# gydrodrive_currentSource.net
KiCad netlist of a schematic drawn in Altium Designer
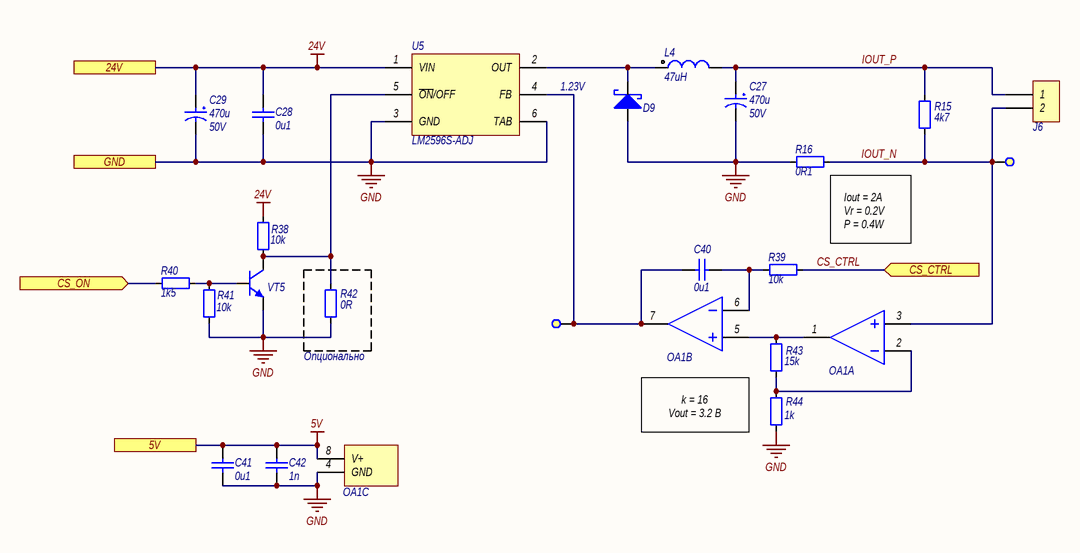
[diagram p0: gydrodrive_currentSource.SchDoc]

(export (version "E")
  (design (tool "Eeschema 10.0.6"))
  (components
    (comp (ref "C27")
      (value "JRB1H471M05001000200000B")
      (footprint "ECAP1020")
      (description "Конденсатор электролитический")
      (fields (field (name "CAPACITANCE") "470u") (field (name "VOLTAGE") "50V"))
      (libsource (lib "StdLib") (part "CAP_POL"))
    )
    (comp (ref "C28")
      (value "CAP_0805")
      (footprint "CAPC2012-0805M")
      (description "Конденсатор керамический, корпус 0805")
      (fields
        (field (name "CAPACITANCE") "0u1")
        (field (name "PART NUMBER") "CAPC_0805")
        (field (name "VOLTAGE") "50V")
      )
      (libsource (lib "StdLib") (part "CAP"))
    )
    (comp (ref "C29")
      (value "JRB1H471M05001000200000B")
      (footprint "ECAP1020")
      (description "Конденсатор электролитический")
      (fields (field (name "CAPACITANCE") "470u") (field (name "VOLTAGE") "50V"))
      (libsource (lib "StdLib") (part "CAP_POL"))
    )
    (comp (ref "C40")
      (value "CAP_0805")
      (footprint "CAPC2012-0805M")
      (description "Конденсатор керамический, корпус 0805")
      (fields
        (field (name "CAPACITANCE") "0u1")
        (field (name "PART NUMBER") "CAPC_0805")
        (field (name "VOLTAGE") "50V")
      )
      (libsource (lib "StdLib") (part "CAP"))
    )
    (comp (ref "C41")
      (value "CAP_0805")
      (footprint "CAPC2012-0805M")
      (description "Конденсатор керамический, корпус 0805")
      (fields
        (field (name "CAPACITANCE") "0u1")
        (field (name "PART NUMBER") "CAPC_0805")
        (field (name "VOLTAGE") "50V")
      )
      (libsource (lib "StdLib") (part "CAP"))
    )
    (comp (ref "C42")
      (value "CAP_0805")
      (footprint "CAPC2012-0805M")
      (description "Конденсатор керамический, корпус 0805")
      (fields
        (field (name "CAPACITANCE") "1n")
        (field (name "PART NUMBER") "CAPC_0805")
        (field (name "VOLTAGE") "50V")
      )
      (libsource (lib "StdLib") (part "CAP"))
    )
    (comp (ref "D9")
      (value "SK56")
      (footprint "SMB_M")
      (description "Диод Шоттки")
      (fields (field (name "VOLTAGE") "60V"))
      (libsource (lib "StdLib") (part "SCHOTTKY"))
    )
    (comp (ref "J6")
      (value "DG142V-5.08-02P")
      (footprint "DG142V-5.08-02P")
      (description "Клеммник 2-контактный, шаг 5.08 мм")
      (libsource (lib "StdLib") (part "PIN1x2"))
    )
    (comp (ref "L4")
      (value "IHLP4040DZER470M11")
      (footprint "IND_IHL4040_M")
      (description "Индуктивность силовая")
      (fields (field (name "INDUCTANCE") "47uH"))
      (libsource (lib "StdLib") (part "IND"))
    )
    (comp (ref "OA1")
      (value "LMV358IDR")
      (footprint "SO8_M")
      (description "Операционный усилитель RTR, маломощный, 2 канала")
      (libsource (lib "") (part "OA_2CH_8PIN_2"))
    )
    (comp (ref "R15")
      (value "RES_1206")
      (footprint "RESC3216-1206M")
      (description "Рез-р, корпус 1206")
      (fields
        (field (name "RESISTANCE") "4k7")
        (field (name "PART NUMBER") "RESC_1206")
        (field (name "TOLERANCE") "5%")
      )
      (libsource (lib "") (part "RES_1"))
    )
    (comp (ref "R16")
      (value "RES_2512")
      (footprint "RESC6332-2512M")
      (description "Рез-р, корпус 2512")
      (fields
        (field (name "RESISTANCE") "0R1")
        (field (name "PART NUMBER") "RESC_2512")
        (field (name "TOLERANCE") "5%")
      )
      (libsource (lib "") (part "RES_2"))
    )
    (comp (ref "R38")
      (value "RES_0805")
      (footprint "RESC2012-0805M")
      (description "Рез-р, корпус 0805")
      (fields
        (field (name "RESISTANCE") "10k")
        (field (name "PART NUMBER") "RESC_0805")
        (field (name "TOLERANCE") "5%")
      )
      (libsource (lib "") (part "RES_1"))
    )
    (comp (ref "R39")
      (value "RES_0805")
      (footprint "RESC2012-0805M")
      (description "Рез-р, корпус 0805")
      (fields
        (field (name "RESISTANCE") "10k")
        (field (name "PART NUMBER") "RESC_0805")
        (field (name "TOLERANCE") "5%")
      )
      (libsource (lib "StdLib") (part "RES"))
    )
    (comp (ref "R40")
      (value "RES_0805")
      (footprint "RESC2012-0805M")
      (description "Рез-р, корпус 0805")
      (fields
        (field (name "RESISTANCE") "1k5")
        (field (name "PART NUMBER") "RESC_0805")
        (field (name "TOLERANCE") "5%")
      )
      (libsource (lib "StdLib") (part "RES"))
    )
    (comp (ref "R41")
      (value "RES_0805")
      (footprint "RESC2012-0805M")
      (description "Рез-р, корпус 0805")
      (fields
        (field (name "RESISTANCE") "10k")
        (field (name "PART NUMBER") "RESC_0805")
        (field (name "TOLERANCE") "5%")
      )
      (libsource (lib "") (part "RES_1"))
    )
    (comp (ref "R42")
      (value "RES_0805")
      (footprint "RESC2012-0805M")
      (description "Рез-р, корпус 0805")
      (fields
        (field (name "RESISTANCE") "0R")
        (field (name "PART NUMBER") "RESC_0805")
        (field (name "TOLERANCE") "5%")
      )
      (libsource (lib "") (part "RES_1"))
    )
    (comp (ref "R43")
      (value "RES_0805")
      (footprint "RESC2012-0805M")
      (description "Рез-р, корпус 0805")
      (fields
        (field (name "RESISTANCE") "15k")
        (field (name "PART NUMBER") "RESC_0805")
        (field (name "TOLERANCE") "5%")
      )
      (libsource (lib "") (part "RES_1"))
    )
    (comp (ref "R44")
      (value "RES_0805")
      (footprint "RESC2012-0805M")
      (description "Рез-р, корпус 0805")
      (fields
        (field (name "RESISTANCE") "1k")
        (field (name "PART NUMBER") "RESC_0805")
        (field (name "TOLERANCE") "5%")
      )
      (libsource (lib "") (part "RES_1"))
    )
    (comp (ref "TP6")
      (value "Test point 1")
      (footprint "TP_1")
      (description "Тестовый контакт круглый 1 мм")
      (libsource (lib "StdLib") (part "Test point"))
    )
    (comp (ref "TP7")
      (value "Test point 1")
      (footprint "TP_1")
      (description "Тестовый контакт круглый 1 мм")
      (libsource (lib "StdLib") (part "Test point"))
    )
    (comp (ref "U5")
      (value "LM2596S-ADJ")
      (footprint "TO-263-5M")
      (description "DC-DC преобразователь")
      (libsource (lib "StdLib") (part "LM2596S-ADJ"))
    )
    (comp (ref "VT5")
      (value "BC817")
      (footprint "SOT23-3M")
      (description "Биполярный транзистор")
      (fields (field (name "VOLTAGE") "45V"))
      (libsource (lib "StdLib") (part "BJT_NPN_SOT23"))
    )
  )
  (nets
    (net (code "1") (name "/CS_CTRL") (class "Default")
      (node (ref "R39") (pin "1") (pinfunction "1_1") (pintype "passive"))
    )
    (net (code "2") (name "/CS_ON") (class "Default")
      (node (ref "R40") (pin "2") (pinfunction "2_2") (pintype "passive"))
    )
    (net (code "3") (name "/IOUT_N") (class "Default")
      (node (ref "J6") (pin "2") (pinfunction "2_2") (pintype "passive"))
      (node (ref "OA1") (pin "3") (pinfunction "INA+_3") (pintype "passive"))
      (node (ref "R15") (pin "1") (pinfunction "1_1") (pintype "passive"))
      (node (ref "R16") (pin "2") (pinfunction "2_2") (pintype "passive"))
      (node (ref "TP6") (pin "1") (pinfunction "1_1") (pintype "passive"))
    )
    (net (code "4") (name "/IOUT_P") (class "Default")
      (node (ref "C27") (pin "1") (pinfunction "1_1") (pintype "passive"))
      (node (ref "J6") (pin "1") (pinfunction "1_1") (pintype "passive"))
      (node (ref "L4") (pin "2") (pinfunction "2_2") (pintype "passive"))
      (node (ref "R15") (pin "2") (pinfunction "2_2") (pintype "passive"))
    )
    (net (code "5") (name "5V") (class "Default")
      (node (ref "C41") (pin "2") (pinfunction "2_2") (pintype "passive"))
      (node (ref "C42") (pin "2") (pinfunction "2_2") (pintype "passive"))
      (node (ref "OA1") (pin "8") (pinfunction "V+_8") (pintype "passive"))
    )
    (net (code "6") (name "24V") (class "Default")
      (node (ref "C28") (pin "1") (pinfunction "1_1") (pintype "passive"))
      (node (ref "C29") (pin "1") (pinfunction "1_1") (pintype "passive"))
      (node (ref "R38") (pin "2") (pinfunction "2_2") (pintype "passive"))
      (node (ref "U5") (pin "1") (pinfunction "VIN_1") (pintype "passive"))
    )
    (net (code "7") (name "GND") (class "Default")
      (node (ref "C27") (pin "2") (pinfunction "2_2") (pintype "passive"))
      (node (ref "C28") (pin "2") (pinfunction "2_2") (pintype "passive"))
      (node (ref "C29") (pin "2") (pinfunction "2_2") (pintype "passive"))
      (node (ref "C41") (pin "1") (pinfunction "1_1") (pintype "passive"))
      (node (ref "C42") (pin "1") (pinfunction "1_1") (pintype "passive"))
      (node (ref "D9") (pin "2") (pinfunction "A_2") (pintype "passive"))
      (node (ref "OA1") (pin "4") (pinfunction "GND_4") (pintype "passive"))
      (node (ref "R16") (pin "1") (pinfunction "1_1") (pintype "passive"))
      (node (ref "R41") (pin "1") (pinfunction "1_1") (pintype "passive"))
      (node (ref "R42") (pin "1") (pinfunction "1_1") (pintype "passive"))
      (node (ref "R44") (pin "1") (pinfunction "1_1") (pintype "passive"))
      (node (ref "U5") (pin "3") (pinfunction "GND_3") (pintype "passive"))
      (node (ref "U5") (pin "6") (pinfunction "TAB_6") (pintype "passive"))
      (node (ref "VT5") (pin "2") (pinfunction "E_2") (pintype "passive"))
    )
    (net (code "8") (name "Net-(D9-K)") (class "Default")
      (node (ref "D9") (pin "1") (pinfunction "K_1") (pintype "passive"))
      (node (ref "L4") (pin "1") (pinfunction "1_1") (pintype "passive"))
      (node (ref "U5") (pin "2") (pinfunction "OUT_2") (pintype "passive"))
    )
    (net (code "9") (name "Net-(OA1A-INA-)") (class "Default")
      (node (ref "OA1") (pin "2") (pinfunction "INA-_2") (pintype "passive"))
      (node (ref "R43") (pin "1") (pinfunction "1_1") (pintype "passive"))
      (node (ref "R44") (pin "2") (pinfunction "2_2") (pintype "passive"))
    )
    (net (code "10") (name "Net-(OA1A-OUTA)") (class "Default")
      (node (ref "OA1") (pin "1") (pinfunction "OUTA_1") (pintype "passive"))
      (node (ref "OA1") (pin "5") (pinfunction "INB+_5") (pintype "passive"))
      (node (ref "R43") (pin "2") (pinfunction "2_2") (pintype "passive"))
    )
    (net (code "11") (name "Net-(OA1B-INB-)") (class "Default")
      (node (ref "C40") (pin "1") (pinfunction "1_1") (pintype "passive"))
      (node (ref "OA1") (pin "6") (pinfunction "INB-_6") (pintype "passive"))
      (node (ref "R39") (pin "2") (pinfunction "2_2") (pintype "passive"))
    )
    (net (code "12") (name "Net-(OA1B-OUTB)") (class "Default")
      (node (ref "C40") (pin "2") (pinfunction "2_2") (pintype "passive"))
      (node (ref "OA1") (pin "7") (pinfunction "OUTB_7") (pintype "passive"))
      (node (ref "TP7") (pin "1") (pinfunction "1_1") (pintype "passive"))
      (node (ref "U5") (pin "4") (pinfunction "FB_4") (pintype "passive"))
    )
    (net (code "13") (name "Net-(U5-~{ON}{slash}OFF)") (class "Default")
      (node (ref "R38") (pin "1") (pinfunction "1_1") (pintype "passive"))
      (node (ref "R42") (pin "2") (pinfunction "2_2") (pintype "passive"))
      (node (ref "U5") (pin "5") (pinfunction "~{ON}/OFF_5") (pintype "passive"))
      (node (ref "VT5") (pin "3") (pinfunction "C_3") (pintype "passive"))
    )
    (net (code "14") (name "Net-(VT5-B)") (class "Default")
      (node (ref "R40") (pin "1") (pinfunction "1_1") (pintype "passive"))
      (node (ref "R41") (pin "2") (pinfunction "2_2") (pintype "passive"))
      (node (ref "VT5") (pin "1") (pinfunction "B_1") (pintype "passive"))
    )
  )
)
